# ecg.net
KiCad netlist of a schematic drawn in EAGLE
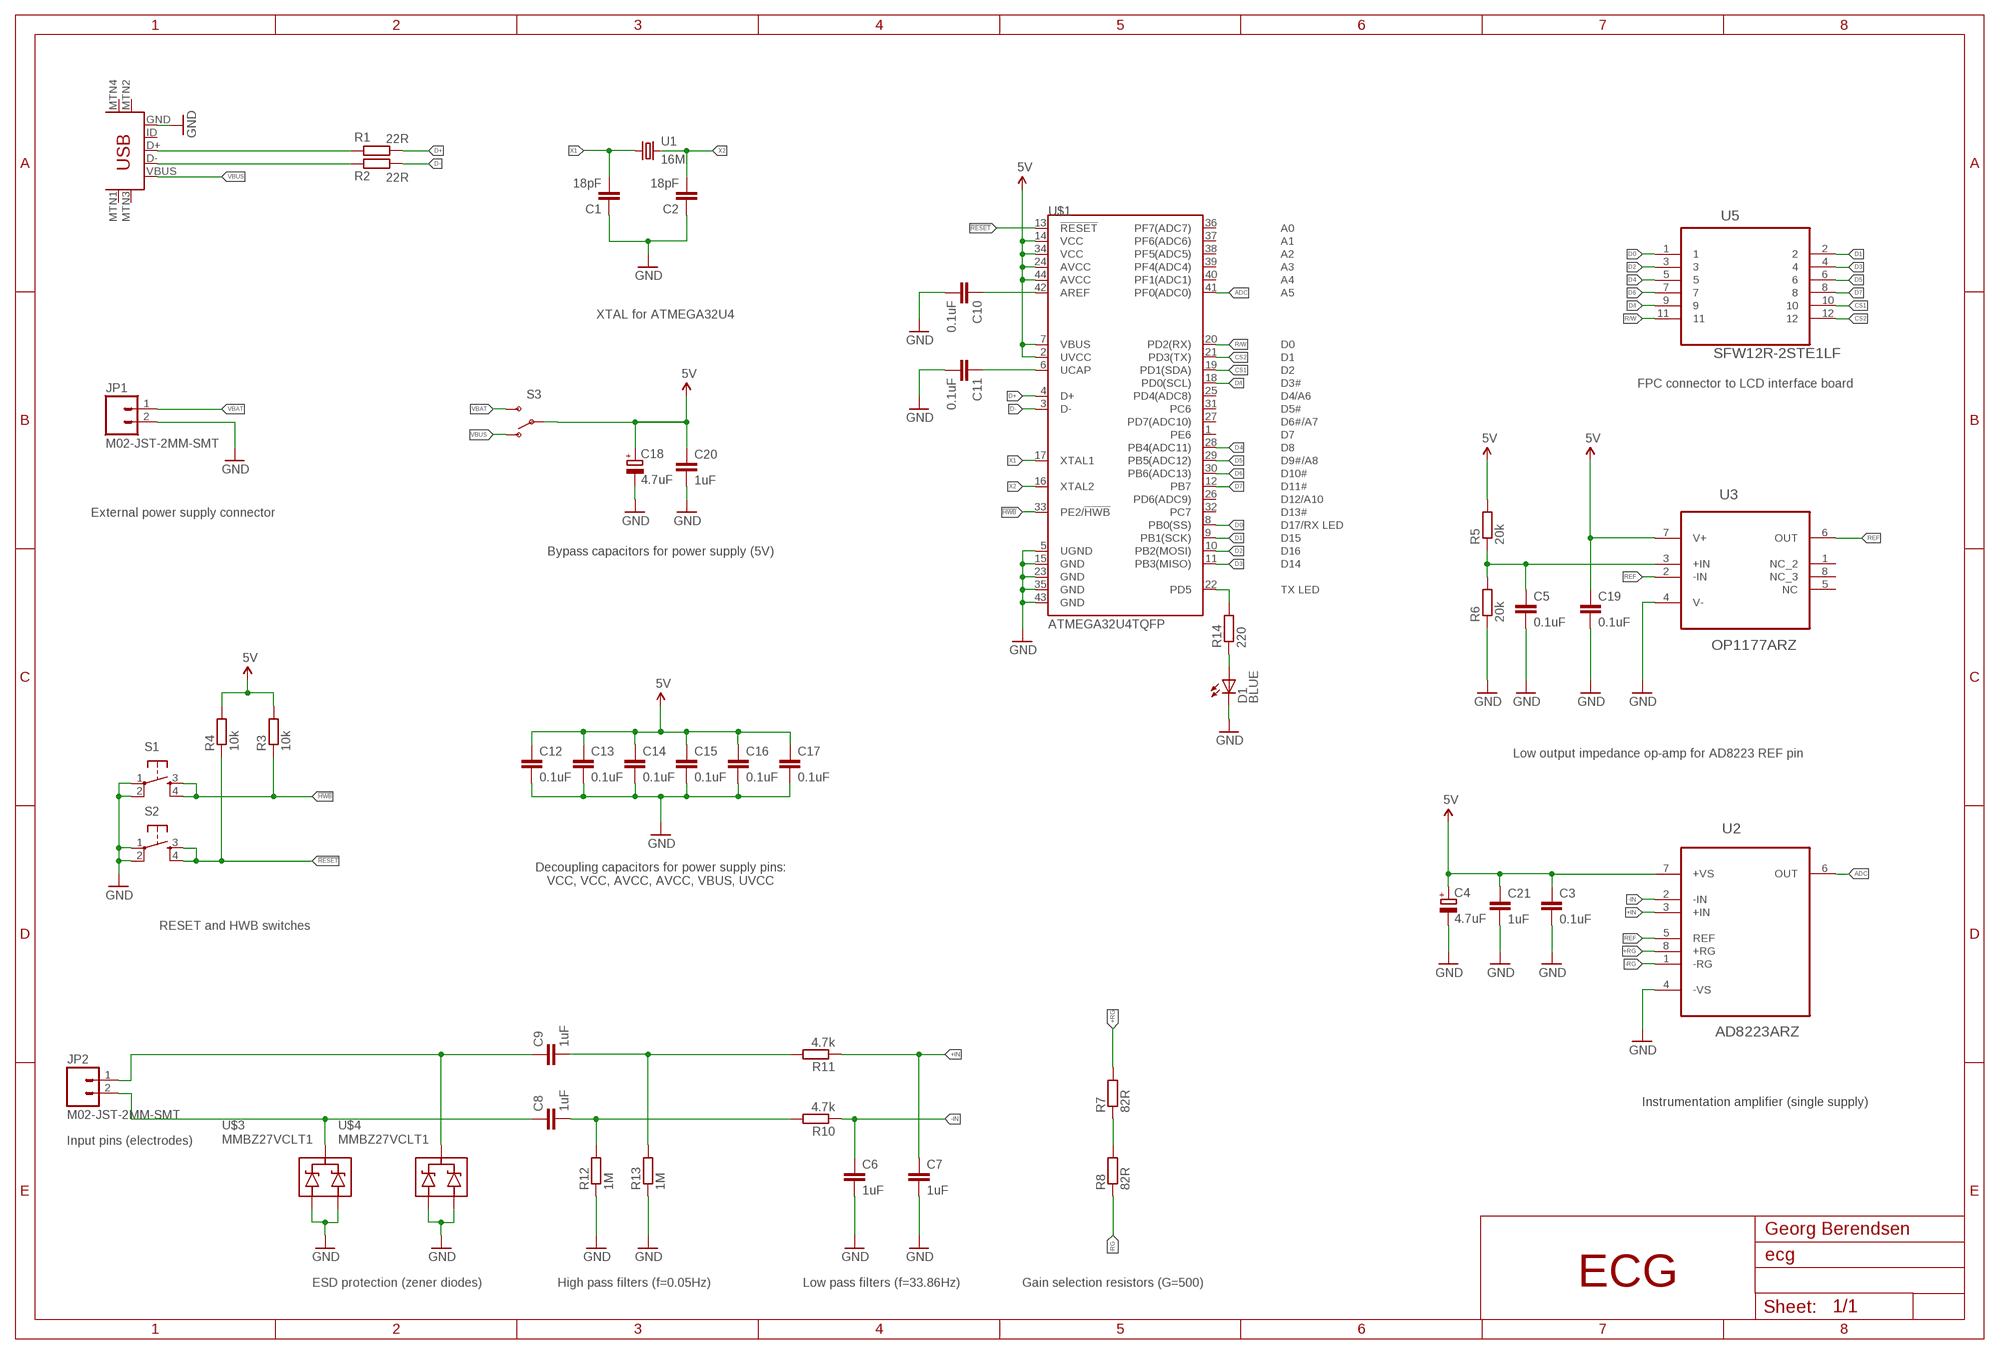
[diagram p0: schematic, sheet 1]

(export (version "E")
  (design (tool "Eeschema 10.0.6"))
  (components
    (comp (ref "C1")
      (value "18pF")
      (footprint "eagle-import:C0603")
      (libsource (lib "eagle-import") (part "C-EUC0603"))
    )
    (comp (ref "C2")
      (value "18pF")
      (footprint "eagle-import:C0603")
      (libsource (lib "eagle-import") (part "C-EUC0603"))
    )
    (comp (ref "C3")
      (value "0.1uF")
      (footprint "eagle-import:C0603")
      (libsource (lib "eagle-import") (part "C-EUC0603"))
    )
    (comp (ref "C4")
      (value "4.7uF")
      (footprint "eagle-import:PANASONIC_A")
      (libsource (lib "eagle-import") (part "CPOL-EUA"))
    )
    (comp (ref "C5")
      (value "0.1uF")
      (footprint "eagle-import:C0603")
      (libsource (lib "eagle-import") (part "C-EUC0603"))
    )
    (comp (ref "C6")
      (value "1uF")
      (footprint "eagle-import:C0603")
      (libsource (lib "eagle-import") (part "C-EUC0603"))
    )
    (comp (ref "C7")
      (value "1uF")
      (footprint "eagle-import:C0603")
      (libsource (lib "eagle-import") (part "C-EUC0603"))
    )
    (comp (ref "C8")
      (value "1uF")
      (footprint "eagle-import:C0603")
      (libsource (lib "eagle-import") (part "C-EUC0603"))
    )
    (comp (ref "C9")
      (value "1uF")
      (footprint "eagle-import:C0603")
      (libsource (lib "eagle-import") (part "C-EUC0603"))
    )
    (comp (ref "C10")
      (value "0.1uF")
      (footprint "eagle-import:C0603")
      (libsource (lib "eagle-import") (part "C-EUC0603"))
    )
    (comp (ref "C11")
      (value "0.1uF")
      (footprint "eagle-import:C0603")
      (libsource (lib "eagle-import") (part "C-EUC0603"))
    )
    (comp (ref "C12")
      (value "0.1uF")
      (footprint "eagle-import:C0603")
      (libsource (lib "eagle-import") (part "C-EUC0603"))
    )
    (comp (ref "C13")
      (value "0.1uF")
      (footprint "eagle-import:C0603")
      (libsource (lib "eagle-import") (part "C-EUC0603"))
    )
    (comp (ref "C14")
      (value "0.1uF")
      (footprint "eagle-import:C0603")
      (libsource (lib "eagle-import") (part "C-EUC0603"))
    )
    (comp (ref "C15")
      (value "0.1uF")
      (footprint "eagle-import:C0603")
      (libsource (lib "eagle-import") (part "C-EUC0603"))
    )
    (comp (ref "C16")
      (value "0.1uF")
      (footprint "eagle-import:C0603")
      (libsource (lib "eagle-import") (part "C-EUC0603"))
    )
    (comp (ref "C17")
      (value "0.1uF")
      (footprint "eagle-import:C0603")
      (libsource (lib "eagle-import") (part "C-EUC0603"))
    )
    (comp (ref "C18")
      (value "4.7uF")
      (footprint "eagle-import:PANASONIC_A")
      (libsource (lib "eagle-import") (part "CPOL-EUA"))
    )
    (comp (ref "C19")
      (value "0.1uF")
      (footprint "eagle-import:C0603")
      (libsource (lib "eagle-import") (part "C-EUC0603"))
    )
    (comp (ref "C20")
      (value "1uF")
      (footprint "eagle-import:C0603")
      (libsource (lib "eagle-import") (part "C-EUC0603"))
    )
    (comp (ref "C21")
      (value "1uF")
      (footprint "eagle-import:C0603")
      (libsource (lib "eagle-import") (part "C-EUC0603"))
    )
    (comp (ref "D1")
      (value "BLUE")
      (footprint "eagle-import:LED-0603")
      (libsource (lib "eagle-import") (part "LED-BLUE0603"))
    )
    (comp (ref "JP1")
      (value "M02-JST-2MM-SMT")
      (footprint "eagle-import:JST-2-SMD")
      (libsource (lib "eagle-import") (part "M02-JST-2MM-SMT"))
    )
    (comp (ref "JP2")
      (value "M02-JST-2MM-SMT")
      (footprint "eagle-import:JST-2-SMD")
      (libsource (lib "eagle-import") (part "M02-JST-2MM-SMT"))
    )
    (comp (ref "R1")
      (value "22R")
      (footprint "eagle-import:R0603")
      (libsource (lib "eagle-import") (part "R-EU_R0603"))
    )
    (comp (ref "R2")
      (value "22R")
      (footprint "eagle-import:R0603")
      (libsource (lib "eagle-import") (part "R-EU_R0603"))
    )
    (comp (ref "R3")
      (value "10k")
      (footprint "eagle-import:R0603")
      (libsource (lib "eagle-import") (part "R-EU_R0603"))
    )
    (comp (ref "R4")
      (value "10k")
      (footprint "eagle-import:R0603")
      (libsource (lib "eagle-import") (part "R-EU_R0603"))
    )
    (comp (ref "R5")
      (value "20k")
      (footprint "eagle-import:R0603")
      (libsource (lib "eagle-import") (part "R-EU_R0603"))
    )
    (comp (ref "R6")
      (value "20k")
      (footprint "eagle-import:R0603")
      (libsource (lib "eagle-import") (part "R-EU_R0603"))
    )
    (comp (ref "R7")
      (value "82R")
      (footprint "eagle-import:R0603")
      (libsource (lib "eagle-import") (part "R-EU_R0603"))
    )
    (comp (ref "R8")
      (value "82R")
      (footprint "eagle-import:R0603")
      (libsource (lib "eagle-import") (part "R-EU_R0603"))
    )
    (comp (ref "R10")
      (value "4.7k")
      (footprint "eagle-import:R0603")
      (libsource (lib "eagle-import") (part "R-EU_R0603"))
    )
    (comp (ref "R11")
      (value "4.7k")
      (footprint "eagle-import:R0603")
      (libsource (lib "eagle-import") (part "R-EU_R0603"))
    )
    (comp (ref "R12")
      (value "1M")
      (footprint "eagle-import:R0603")
      (libsource (lib "eagle-import") (part "R-EU_R0603"))
    )
    (comp (ref "R13")
      (value "1M")
      (footprint "eagle-import:R0603")
      (libsource (lib "eagle-import") (part "R-EU_R0603"))
    )
    (comp (ref "R14")
      (value "220")
      (footprint "eagle-import:R0603")
      (libsource (lib "eagle-import") (part "R-EU_R0603"))
    )
    (comp (ref "S1")
      (value "TAC_SWITCHSMD")
      (footprint "eagle-import:TACTILE_SWITCH_SMD")
      (libsource (lib "eagle-import") (part "TAC_SWITCHSMD"))
    )
    (comp (ref "S2")
      (value "TAC_SWITCHSMD")
      (footprint "eagle-import:TACTILE_SWITCH_SMD")
      (libsource (lib "eagle-import") (part "TAC_SWITCHSMD"))
    )
    (comp (ref "S3")
      (value "SWITCH-SPDTSMD2")
      (footprint "eagle-import:SWITCH-SPDT-SMD")
      (libsource (lib "eagle-import") (part "SWITCH-SPDTSMD2"))
    )
    (comp (ref "U$1")
      (value "ATMEGA32U4TQFP")
      (footprint "eagle-import:SPARKFUN-DIGITALIC_TQFP44")
      (libsource (lib "eagle-import") (part "ATMEGA32U4TQFP"))
    )
    (comp (ref "U$2")
      (value "USB-MINIB-5PIN")
      (footprint "eagle-import:USB-MINIB")
      (libsource (lib "eagle-import") (part "USB-MINIB-5PIN"))
    )
    (comp (ref "U$3")
      (value "MMBZ27VCLT1")
      (footprint "eagle-import:SOT23-3")
      (libsource (lib "eagle-import") (part "MMBZ27VCLT1"))
    )
    (comp (ref "U$4")
      (value "MMBZ27VCLT1")
      (footprint "eagle-import:SOT23-3")
      (libsource (lib "eagle-import") (part "MMBZ27VCLT1"))
    )
    (comp (ref "U1")
      (value "16M")
      (footprint "eagle-import:CRYSTAL-SMD-5X3")
      (libsource (lib "eagle-import") (part "CRYSTAL5X3"))
    )
    (comp (ref "U2")
      (value "AD8223ARZ")
      (footprint "eagle-import:SOIC127P600X175-8N")
      (libsource (lib "eagle-import") (part "AD8223ARZ"))
    )
    (comp (ref "U3")
      (value "OP1177ARZ")
      (footprint "eagle-import:SOIC127P600X175-8N")
      (libsource (lib "eagle-import") (part "OP1177ARZ"))
    )
    (comp (ref "U5")
      (value "SFW12R-2STE1LF")
      (footprint "eagle-import:FCI_SFW12R-2STE1LF")
      (libsource (lib "eagle-import") (part "SFW12R-2STE1LF"))
    )
  )
  (nets
    (net (code "1") (name "+IN") (class "Default")
      (node (ref "C7") (pin "1") (pinfunction "1_1") (pintype "passive"))
      (node (ref "R11") (pin "1") (pinfunction "1_1") (pintype "passive"))
      (node (ref "U2") (pin "3") (pinfunction "+IN_3") (pintype "input"))
    )
    (net (code "2") (name "+RG") (class "Default")
      (node (ref "R7") (pin "2") (pinfunction "2_2") (pintype "passive"))
      (node (ref "U2") (pin "8") (pinfunction "+RG_8") (pintype "passive"))
    )
    (net (code "3") (name "-IN") (class "Default")
      (node (ref "C6") (pin "1") (pinfunction "1_1") (pintype "passive"))
      (node (ref "R10") (pin "1") (pinfunction "1_1") (pintype "passive"))
      (node (ref "U2") (pin "2") (pinfunction "-IN_2") (pintype "input"))
    )
    (net (code "4") (name "-RG") (class "Default")
      (node (ref "R8") (pin "1") (pinfunction "1_1") (pintype "passive"))
      (node (ref "U2") (pin "1") (pinfunction "-RG_1") (pintype "passive"))
    )
    (net (code "5") (name "/~{HWB}") (class "Default")
      (node (ref "R3") (pin "1") (pinfunction "1_1") (pintype "passive"))
      (node (ref "S1") (pin "3") (pinfunction "3_3") (pintype "passive"))
      (node (ref "S1") (pin "4") (pinfunction "4_4") (pintype "passive"))
      (node (ref "U$1") (pin "33") (pinfunction "PE2/~{HWB}_33") (pintype "bidirectional"))
    )
    (net (code "6") (name "/~{RESET}") (class "Default")
      (node (ref "R4") (pin "1") (pinfunction "1_1") (pintype "passive"))
      (node (ref "S2") (pin "3") (pinfunction "3_3") (pintype "passive"))
      (node (ref "S2") (pin "4") (pinfunction "4_4") (pintype "passive"))
      (node (ref "U$1") (pin "13") (pinfunction "~{RESET}_13") (pintype "bidirectional"))
    )
    (net (code "7") (name "5V") (class "Default")
      (node (ref "C12") (pin "1") (pinfunction "1_1") (pintype "passive"))
      (node (ref "C13") (pin "1") (pinfunction "1_1") (pintype "passive"))
      (node (ref "C14") (pin "1") (pinfunction "1_1") (pintype "passive"))
      (node (ref "C15") (pin "1") (pinfunction "1_1") (pintype "passive"))
      (node (ref "C16") (pin "1") (pinfunction "1_1") (pintype "passive"))
      (node (ref "C17") (pin "1") (pinfunction "1_1") (pintype "passive"))
      (node (ref "C18") (pin "+") (pinfunction "+_+") (pintype "passive"))
      (node (ref "C19") (pin "1") (pinfunction "1_1") (pintype "passive"))
      (node (ref "C20") (pin "1") (pinfunction "1_1") (pintype "passive"))
      (node (ref "C21") (pin "1") (pinfunction "1_1") (pintype "passive"))
      (node (ref "C3") (pin "1") (pinfunction "1_1") (pintype "passive"))
      (node (ref "C4") (pin "+") (pinfunction "+_+") (pintype "passive"))
      (node (ref "R3") (pin "2") (pinfunction "2_2") (pintype "passive"))
      (node (ref "R4") (pin "2") (pinfunction "2_2") (pintype "passive"))
      (node (ref "R5") (pin "2") (pinfunction "2_2") (pintype "passive"))
      (node (ref "S3") (pin "2") (pinfunction "P_2") (pintype "passive"))
      (node (ref "U$1") (pin "14") (pinfunction "VCC_14") (pintype "bidirectional"))
      (node (ref "U$1") (pin "2") (pinfunction "UVCC_2") (pintype "bidirectional"))
      (node (ref "U$1") (pin "24") (pinfunction "AVCC_24") (pintype "bidirectional"))
      (node (ref "U$1") (pin "34") (pinfunction "VCC_34") (pintype "bidirectional"))
      (node (ref "U$1") (pin "44") (pinfunction "AVCC_44") (pintype "bidirectional"))
      (node (ref "U$1") (pin "7") (pinfunction "VBUS_7") (pintype "bidirectional"))
      (node (ref "U2") (pin "7") (pinfunction "+VS_7") (pintype "power_in"))
      (node (ref "U3") (pin "7") (pinfunction "V+_7") (pintype "power_in"))
    )
    (net (code "8") (name "ADC") (class "Default")
      (node (ref "U$1") (pin "41") (pinfunction "PF0(ADC0)_41") (pintype "bidirectional"))
      (node (ref "U2") (pin "6") (pinfunction "OUT_6") (pintype "output"))
    )
    (net (code "9") (name "CS1") (class "Default")
      (node (ref "U$1") (pin "19") (pinfunction "PD1(SDA)_19") (pintype "bidirectional"))
      (node (ref "U5") (pin "10") (pinfunction "10_10") (pintype "passive"))
    )
    (net (code "10") (name "CS2") (class "Default")
      (node (ref "U$1") (pin "21") (pinfunction "PD3(TX)_21") (pintype "bidirectional"))
      (node (ref "U5") (pin "12") (pinfunction "12_12") (pintype "passive"))
    )
    (net (code "11") (name "D+") (class "Default")
      (node (ref "R1") (pin "1") (pinfunction "1_1") (pintype "passive"))
      (node (ref "U$1") (pin "4") (pinfunction "D+_4") (pintype "bidirectional"))
    )
    (net (code "12") (name "D-") (class "Default")
      (node (ref "R2") (pin "1") (pinfunction "1_1") (pintype "passive"))
      (node (ref "U$1") (pin "3") (pinfunction "D-_3") (pintype "bidirectional"))
    )
    (net (code "13") (name "D0") (class "Default")
      (node (ref "U$1") (pin "8") (pinfunction "PB0(SS)_8") (pintype "bidirectional"))
      (node (ref "U5") (pin "1") (pinfunction "1_1") (pintype "passive"))
    )
    (net (code "14") (name "D1") (class "Default")
      (node (ref "U$1") (pin "9") (pinfunction "PB1(SCK)_9") (pintype "bidirectional"))
      (node (ref "U5") (pin "2") (pinfunction "2_2") (pintype "passive"))
    )
    (net (code "15") (name "D2") (class "Default")
      (node (ref "U$1") (pin "10") (pinfunction "PB2(MOSI)_10") (pintype "bidirectional"))
      (node (ref "U5") (pin "3") (pinfunction "3_3") (pintype "passive"))
    )
    (net (code "16") (name "D3") (class "Default")
      (node (ref "U$1") (pin "11") (pinfunction "PB3(MISO)_11") (pintype "bidirectional"))
      (node (ref "U5") (pin "4") (pinfunction "4_4") (pintype "passive"))
    )
    (net (code "17") (name "D4") (class "Default")
      (node (ref "U$1") (pin "28") (pinfunction "PB4(ADC11)_28") (pintype "bidirectional"))
      (node (ref "U5") (pin "5") (pinfunction "5_5") (pintype "passive"))
    )
    (net (code "18") (name "D5") (class "Default")
      (node (ref "U$1") (pin "29") (pinfunction "PB5(ADC12)_29") (pintype "bidirectional"))
      (node (ref "U5") (pin "6") (pinfunction "6_6") (pintype "passive"))
    )
    (net (code "19") (name "D6") (class "Default")
      (node (ref "U$1") (pin "30") (pinfunction "PB6(ADC13)_30") (pintype "bidirectional"))
      (node (ref "U5") (pin "7") (pinfunction "7_7") (pintype "passive"))
    )
    (net (code "20") (name "D7") (class "Default")
      (node (ref "U$1") (pin "12") (pinfunction "PB7_12") (pintype "bidirectional"))
      (node (ref "U5") (pin "8") (pinfunction "8_8") (pintype "passive"))
    )
    (net (code "21") (name "D{slash}I") (class "Default")
      (node (ref "U$1") (pin "18") (pinfunction "PD0(SCL)_18") (pintype "bidirectional"))
      (node (ref "U5") (pin "9") (pinfunction "9_9") (pintype "passive"))
    )
    (net (code "22") (name "GND") (class "Default")
      (node (ref "C1") (pin "1") (pinfunction "1_1") (pintype "passive"))
      (node (ref "C10") (pin "2") (pinfunction "2_2") (pintype "passive"))
      (node (ref "C11") (pin "2") (pinfunction "2_2") (pintype "passive"))
      (node (ref "C12") (pin "2") (pinfunction "2_2") (pintype "passive"))
      (node (ref "C13") (pin "2") (pinfunction "2_2") (pintype "passive"))
      (node (ref "C14") (pin "2") (pinfunction "2_2") (pintype "passive"))
      (node (ref "C15") (pin "2") (pinfunction "2_2") (pintype "passive"))
      (node (ref "C16") (pin "2") (pinfunction "2_2") (pintype "passive"))
      (node (ref "C17") (pin "2") (pinfunction "2_2") (pintype "passive"))
      (node (ref "C18") (pin "-") (pinfunction "-_-") (pintype "passive"))
      (node (ref "C19") (pin "2") (pinfunction "2_2") (pintype "passive"))
      (node (ref "C2") (pin "1") (pinfunction "1_1") (pintype "passive"))
      (node (ref "C20") (pin "2") (pinfunction "2_2") (pintype "passive"))
      (node (ref "C21") (pin "2") (pinfunction "2_2") (pintype "passive"))
      (node (ref "C3") (pin "2") (pinfunction "2_2") (pintype "passive"))
      (node (ref "C4") (pin "-") (pinfunction "-_-") (pintype "passive"))
      (node (ref "C5") (pin "2") (pinfunction "2_2") (pintype "passive"))
      (node (ref "C6") (pin "2") (pinfunction "2_2") (pintype "passive"))
      (node (ref "C7") (pin "2") (pinfunction "2_2") (pintype "passive"))
      (node (ref "D1") (pin "C") (pinfunction "C_C") (pintype "passive"))
      (node (ref "JP1") (pin "2") (pinfunction "1_2") (pintype "passive"))
      (node (ref "R12") (pin "1") (pinfunction "1_1") (pintype "passive"))
      (node (ref "R13") (pin "1") (pinfunction "1_1") (pintype "passive"))
      (node (ref "R6") (pin "1") (pinfunction "1_1") (pintype "passive"))
      (node (ref "S1") (pin "1") (pinfunction "1_1") (pintype "passive"))
      (node (ref "S1") (pin "2") (pinfunction "2_2") (pintype "passive"))
      (node (ref "S2") (pin "1") (pinfunction "1_1") (pintype "passive"))
      (node (ref "S2") (pin "2") (pinfunction "2_2") (pintype "passive"))
      (node (ref "U$1") (pin "15") (pinfunction "GND_15") (pintype "bidirectional"))
      (node (ref "U$1") (pin "23") (pinfunction "GND_23") (pintype "bidirectional"))
      (node (ref "U$1") (pin "35") (pinfunction "GND_35") (pintype "bidirectional"))
      (node (ref "U$1") (pin "43") (pinfunction "GND_43") (pintype "bidirectional"))
      (node (ref "U$1") (pin "5") (pinfunction "UGND_5") (pintype "bidirectional"))
      (node (ref "U$2") (pin "GND") (pinfunction "GND_GND") (pintype "bidirectional"))
      (node (ref "U$3") (pin "1") (pinfunction "A1_1") (pintype "passive"))
      (node (ref "U$3") (pin "2") (pinfunction "A2_2") (pintype "passive"))
      (node (ref "U$4") (pin "1") (pinfunction "A1_1") (pintype "passive"))
      (node (ref "U$4") (pin "2") (pinfunction "A2_2") (pintype "passive"))
      (node (ref "U2") (pin "4") (pinfunction "-VS_4") (pintype "power_in"))
      (node (ref "U3") (pin "4") (pinfunction "V-_4") (pintype "power_in"))
    )
    (net (code "23") (name "Net-(C8-Pad2)") (class "Default")
      (node (ref "C8") (pin "2") (pinfunction "2_2") (pintype "passive"))
      (node (ref "R10") (pin "2") (pinfunction "2_2") (pintype "passive"))
      (node (ref "R12") (pin "2") (pinfunction "2_2") (pintype "passive"))
    )
    (net (code "24") (name "Net-(C9-Pad2)") (class "Default")
      (node (ref "C9") (pin "2") (pinfunction "2_2") (pintype "passive"))
      (node (ref "R11") (pin "2") (pinfunction "2_2") (pintype "passive"))
      (node (ref "R13") (pin "2") (pinfunction "2_2") (pintype "passive"))
    )
    (net (code "25") (name "Net-(D1-PadA)") (class "Default")
      (node (ref "D1") (pin "A") (pinfunction "A_A") (pintype "passive"))
      (node (ref "R14") (pin "1") (pinfunction "1_1") (pintype "passive"))
    )
    (net (code "26") (name "Net-(JP2-1)") (class "Default")
      (node (ref "C8") (pin "1") (pinfunction "1_1") (pintype "passive"))
      (node (ref "JP2") (pin "2") (pinfunction "1_2") (pintype "passive"))
      (node (ref "U$3") (pin "3") (pinfunction "C_3") (pintype "passive"))
    )
    (net (code "27") (name "Net-(JP2-2)") (class "Default")
      (node (ref "C9") (pin "1") (pinfunction "1_1") (pintype "passive"))
      (node (ref "JP2") (pin "1") (pinfunction "2_1") (pintype "passive"))
      (node (ref "U$4") (pin "3") (pinfunction "C_3") (pintype "passive"))
    )
    (net (code "28") (name "Net-(R1-Pad2)") (class "Default")
      (node (ref "R1") (pin "2") (pinfunction "2_2") (pintype "passive"))
      (node (ref "U$2") (pin "D+") (pinfunction "D+_D+") (pintype "bidirectional"))
    )
    (net (code "29") (name "Net-(R2-Pad2)") (class "Default")
      (node (ref "R2") (pin "2") (pinfunction "2_2") (pintype "passive"))
      (node (ref "U$2") (pin "D-") (pinfunction "D-_D-") (pintype "bidirectional"))
    )
    (net (code "30") (name "Net-(R7-Pad1)") (class "Default")
      (node (ref "R7") (pin "1") (pinfunction "1_1") (pintype "passive"))
      (node (ref "R8") (pin "2") (pinfunction "2_2") (pintype "passive"))
    )
    (net (code "31") (name "Net-(U$1-AREF)") (class "Default")
      (node (ref "C10") (pin "1") (pinfunction "1_1") (pintype "passive"))
      (node (ref "U$1") (pin "42") (pinfunction "AREF_42") (pintype "bidirectional"))
    )
    (net (code "32") (name "Net-(U$1-PD5)") (class "Default")
      (node (ref "R14") (pin "2") (pinfunction "2_2") (pintype "passive"))
      (node (ref "U$1") (pin "22") (pinfunction "PD5_22") (pintype "bidirectional"))
    )
    (net (code "33") (name "Net-(U$1-UCAP)") (class "Default")
      (node (ref "C11") (pin "1") (pinfunction "1_1") (pintype "passive"))
      (node (ref "U$1") (pin "6") (pinfunction "UCAP_6") (pintype "bidirectional"))
    )
    (net (code "34") (name "Net-(U3-+IN)") (class "Default")
      (node (ref "C5") (pin "1") (pinfunction "1_1") (pintype "passive"))
      (node (ref "R5") (pin "1") (pinfunction "1_1") (pintype "passive"))
      (node (ref "R6") (pin "2") (pinfunction "2_2") (pintype "passive"))
      (node (ref "U3") (pin "3") (pinfunction "+IN_3") (pintype "input"))
    )
    (net (code "35") (name "REF") (class "Default")
      (node (ref "U2") (pin "5") (pinfunction "REF_5") (pintype "input"))
      (node (ref "U3") (pin "2") (pinfunction "-IN_2") (pintype "input"))
      (node (ref "U3") (pin "6") (pinfunction "OUT_6") (pintype "output"))
    )
    (net (code "36") (name "R{slash}W") (class "Default")
      (node (ref "U$1") (pin "20") (pinfunction "PD2(RX)_20") (pintype "bidirectional"))
      (node (ref "U5") (pin "11") (pinfunction "11_11") (pintype "passive"))
    )
    (net (code "37") (name "VBAT") (class "Default")
      (node (ref "JP1") (pin "1") (pinfunction "2_1") (pintype "passive"))
      (node (ref "S3") (pin "3") (pinfunction "S_3") (pintype "passive"))
    )
    (net (code "38") (name "VBUS") (class "Default")
      (node (ref "S3") (pin "1") (pinfunction "O_1") (pintype "passive"))
      (node (ref "U$2") (pin "VBUS") (pinfunction "VBUS_VBUS") (pintype "bidirectional"))
    )
    (net (code "39") (name "X1") (class "Default")
      (node (ref "C1") (pin "2") (pinfunction "2_2") (pintype "passive"))
      (node (ref "U$1") (pin "17") (pinfunction "XTAL1_17") (pintype "bidirectional"))
      (node (ref "U1") (pin "1") (pinfunction "1_1") (pintype "passive"))
    )
    (net (code "40") (name "X2") (class "Default")
      (node (ref "C2") (pin "2") (pinfunction "2_2") (pintype "passive"))
      (node (ref "U$1") (pin "16") (pinfunction "XTAL2_16") (pintype "bidirectional"))
      (node (ref "U1") (pin "3") (pinfunction "2_3") (pintype "passive"))
    )
    (net (code "41") (name "unconnected-(U$1-PC6-Pad31)") (class "Default")
      (node (ref "U$1") (pin "31") (pinfunction "PC6_31") (pintype "bidirectional"))
    )
    (net (code "42") (name "unconnected-(U$1-PC7-Pad32)") (class "Default")
      (node (ref "U$1") (pin "32") (pinfunction "PC7_32") (pintype "bidirectional"))
    )
    (net (code "43") (name "unconnected-(U$1-PD4(ADC8)-Pad25)") (class "Default")
      (node (ref "U$1") (pin "25") (pinfunction "PD4(ADC8)_25") (pintype "bidirectional"))
    )
    (net (code "44") (name "unconnected-(U$1-PD6(ADC9)-Pad26)") (class "Default")
      (node (ref "U$1") (pin "26") (pinfunction "PD6(ADC9)_26") (pintype "bidirectional"))
    )
    (net (code "45") (name "unconnected-(U$1-PD7(ADC10)-Pad27)") (class "Default")
      (node (ref "U$1") (pin "27") (pinfunction "PD7(ADC10)_27") (pintype "bidirectional"))
    )
    (net (code "46") (name "unconnected-(U$1-PE6-Pad1)") (class "Default")
      (node (ref "U$1") (pin "1") (pinfunction "PE6_1") (pintype "bidirectional"))
    )
    (net (code "47") (name "unconnected-(U$1-PF1(ADC1)-Pad40)") (class "Default")
      (node (ref "U$1") (pin "40") (pinfunction "PF1(ADC1)_40") (pintype "bidirectional"))
    )
    (net (code "48") (name "unconnected-(U$1-PF4(ADC4)-Pad39)") (class "Default")
      (node (ref "U$1") (pin "39") (pinfunction "PF4(ADC4)_39") (pintype "bidirectional"))
    )
    (net (code "49") (name "unconnected-(U$1-PF5(ADC5)-Pad38)") (class "Default")
      (node (ref "U$1") (pin "38") (pinfunction "PF5(ADC5)_38") (pintype "bidirectional"))
    )
    (net (code "50") (name "unconnected-(U$1-PF6(ADC6)-Pad37)") (class "Default")
      (node (ref "U$1") (pin "37") (pinfunction "PF6(ADC6)_37") (pintype "bidirectional"))
    )
    (net (code "51") (name "unconnected-(U$1-PF7(ADC7)-Pad36)") (class "Default")
      (node (ref "U$1") (pin "36") (pinfunction "PF7(ADC7)_36") (pintype "bidirectional"))
    )
    (net (code "52") (name "unconnected-(U$2-MTN1-PadMTN3)") (class "Default")
      (node (ref "U$2") (pin "MTN3") (pinfunction "MTN1_MTN3") (pintype "bidirectional"))
    )
    (net (code "53") (name "unconnected-(U$2-MTN2-PadMTN1)") (class "Default")
      (node (ref "U$2") (pin "MTN1") (pinfunction "MTN2_MTN1") (pintype "bidirectional"))
    )
    (net (code "54") (name "unconnected-(U$2-MTN3-PadMTN2)") (class "Default")
      (node (ref "U$2") (pin "MTN2") (pinfunction "MTN3_MTN2") (pintype "bidirectional"))
    )
    (net (code "55") (name "unconnected-(U$2-PadID)") (class "Default")
      (node (ref "U$2") (pin "ID") (pinfunction "ID_ID") (pintype "bidirectional"))
    )
    (net (code "56") (name "unconnected-(U$2-PadMTN4)") (class "Default")
      (node (ref "U$2") (pin "MTN4") (pinfunction "MTN4_MTN4") (pintype "bidirectional"))
    )
    (net (code "57") (name "unconnected-(U3-NC-Pad5)") (class "Default")
      (node (ref "U3") (pin "5") (pinfunction "NC_5") (pintype "no_connect"))
    )
    (net (code "58") (name "unconnected-(U3-NC_2-Pad1)") (class "Default")
      (node (ref "U3") (pin "1") (pinfunction "NC_2_1") (pintype "no_connect"))
    )
    (net (code "59") (name "unconnected-(U3-NC_3-Pad8)") (class "Default")
      (node (ref "U3") (pin "8") (pinfunction "NC_3_8") (pintype "no_connect"))
    )
  )
)
